# PlugEVSE_Main.net
KiCad netlist of a schematic drawn in EAGLE
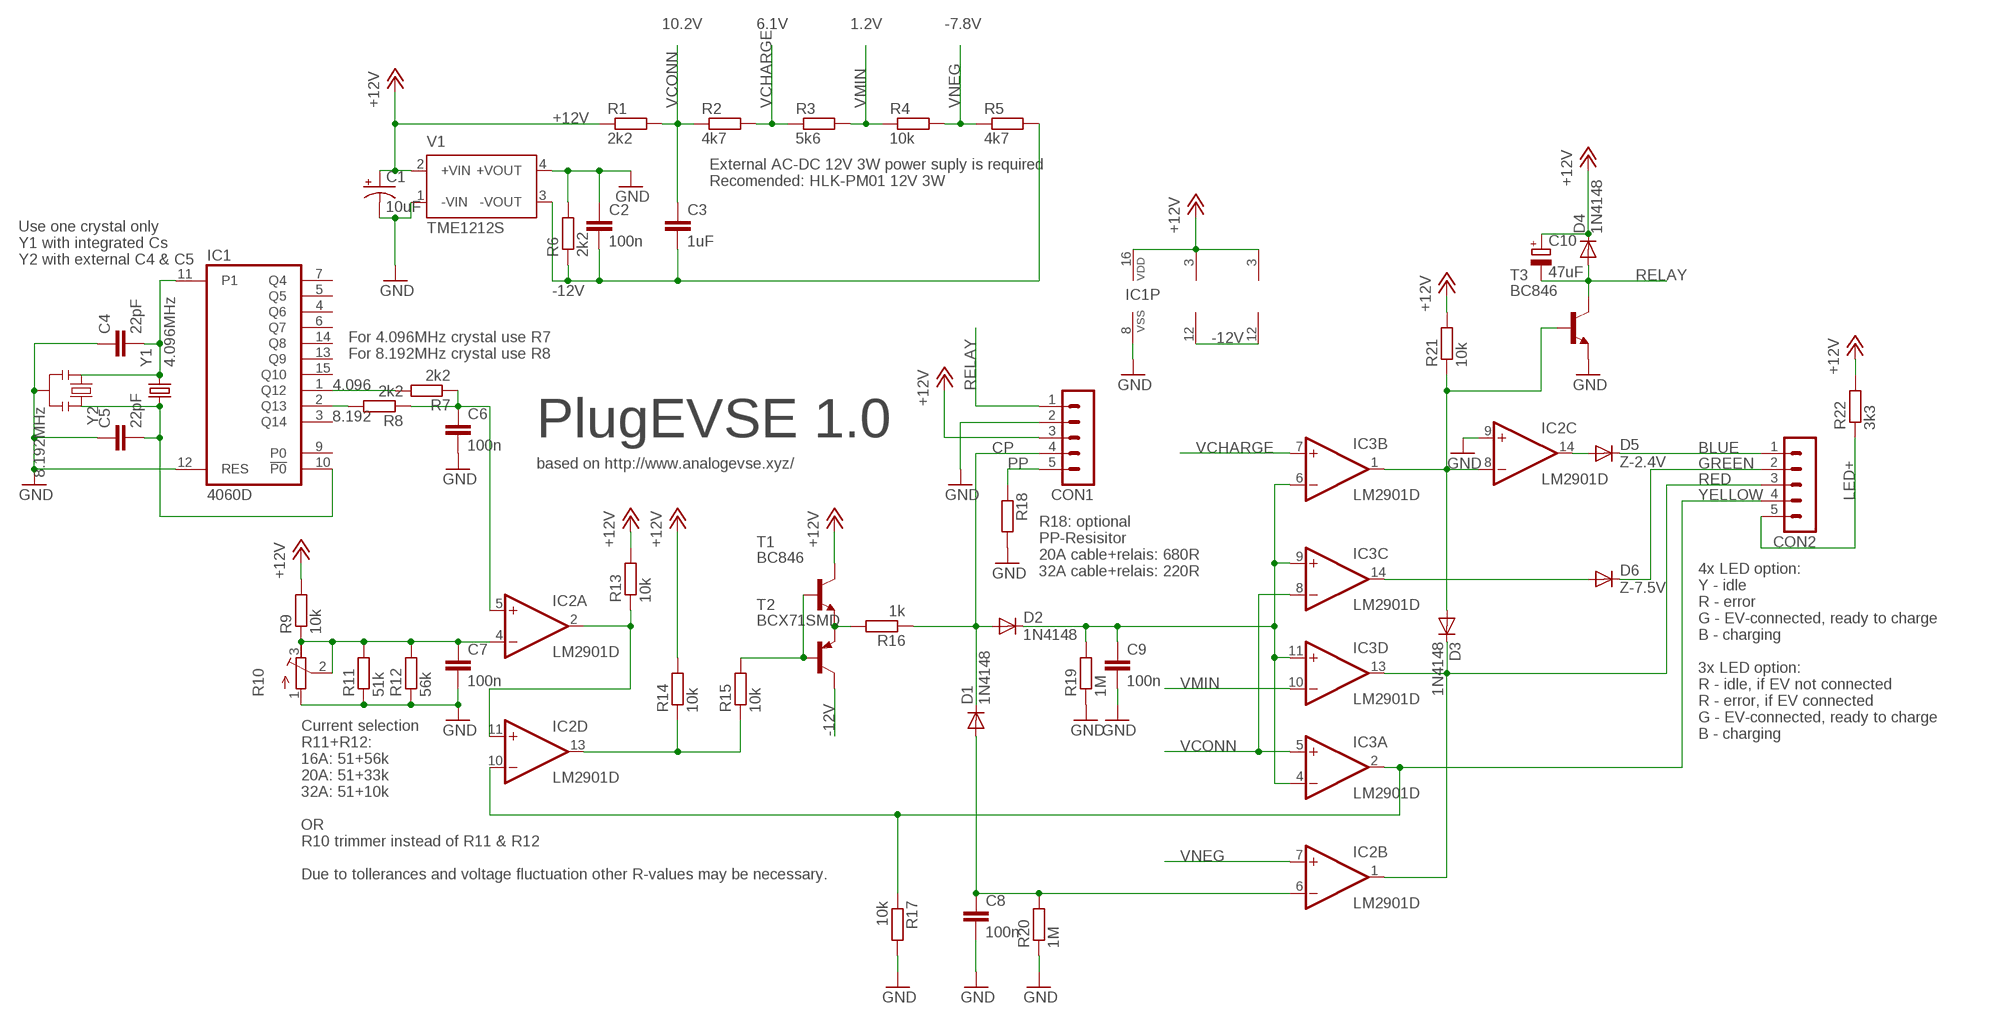
[diagram p0: schematic, sheet 1]

(export (version "E")
  (design (tool "Eeschema 10.0.6"))
  (components
    (comp (ref "C1")
      (value "10uF")
      (footprint "eagle-import:EIA3216")
      (libsource (lib "eagle-import") (part "CAP_POL1206"))
    )
    (comp (ref "C2")
      (value "100n")
      (footprint "eagle-import:C0603")
      (libsource (lib "eagle-import") (part "C-EUC0603"))
    )
    (comp (ref "C3")
      (value "1uF")
      (footprint "eagle-import:C0603")
      (libsource (lib "eagle-import") (part "C-EUC0603"))
    )
    (comp (ref "C4")
      (value "22pF")
      (footprint "eagle-import:C0603")
      (libsource (lib "eagle-import") (part "C-EUC0603"))
    )
    (comp (ref "C5")
      (value "22pF")
      (footprint "eagle-import:C0603")
      (libsource (lib "eagle-import") (part "C-EUC0603"))
    )
    (comp (ref "C6")
      (value "100n")
      (footprint "eagle-import:C0603")
      (libsource (lib "eagle-import") (part "C-EUC0603"))
    )
    (comp (ref "C7")
      (value "100n")
      (footprint "eagle-import:C0603")
      (libsource (lib "eagle-import") (part "C-EUC0603"))
    )
    (comp (ref "C8")
      (value "100n")
      (footprint "eagle-import:C0603")
      (libsource (lib "eagle-import") (part "C-EUC0603"))
    )
    (comp (ref "C9")
      (value "100n")
      (footprint "eagle-import:C0603")
      (libsource (lib "eagle-import") (part "C-EUC0603"))
    )
    (comp (ref "C10")
      (value "47uF")
      (footprint "eagle-import:E2,5-5")
      (libsource (lib "eagle-import") (part "CPOL-EUE2.5-5"))
    )
    (comp (ref "CON1")
      (value "MA05-1")
      (footprint "eagle-import:MA05-1")
      (libsource (lib "eagle-import") (part "MA05-1"))
    )
    (comp (ref "CON2")
      (value "MA05-1")
      (footprint "eagle-import:MA05-1")
      (libsource (lib "eagle-import") (part "MA05-1"))
    )
    (comp (ref "D1")
      (value "1N4148")
      (footprint "eagle-import:SOD123")
      (libsource (lib "eagle-import") (part "DIODE-SOD123"))
    )
    (comp (ref "D2")
      (value "1N4148")
      (footprint "eagle-import:SOD123")
      (libsource (lib "eagle-import") (part "DIODE-SOD123"))
    )
    (comp (ref "D3")
      (value "1N4148")
      (footprint "eagle-import:SOD123")
      (libsource (lib "eagle-import") (part "DIODE-SOD123"))
    )
    (comp (ref "D4")
      (value "1N4148")
      (footprint "eagle-import:SOD123")
      (libsource (lib "eagle-import") (part "DIODE-SOD123"))
    )
    (comp (ref "D5")
      (value "Z-2.4V")
      (footprint "eagle-import:SOD123")
      (libsource (lib "eagle-import") (part "DIODE-SOD123"))
    )
    (comp (ref "D6")
      (value "Z-7.5V")
      (footprint "eagle-import:SOD123")
      (libsource (lib "eagle-import") (part "DIODE-SOD123"))
    )
    (comp (ref "IC1")
      (value "4060D")
      (footprint "eagle-import:SO16")
      (libsource (lib "eagle-import") (part "4060D"))
    )
    (comp (ref "IC2")
      (value "LM2901D")
      (footprint "eagle-import:SO14")
      (libsource (lib "eagle-import") (part "LM2901D"))
    )
    (comp (ref "IC3")
      (value "LM2901D")
      (footprint "eagle-import:SO14")
      (libsource (lib "eagle-import") (part "LM2901D"))
    )
    (comp (ref "R1")
      (value "2k2")
      (footprint "eagle-import:R0603")
      (libsource (lib "eagle-import") (part "rcl_334_R-EU_R0603"))
    )
    (comp (ref "R2")
      (value "4k7")
      (footprint "eagle-import:R0603")
      (libsource (lib "eagle-import") (part "rcl_334_R-EU_R0603"))
    )
    (comp (ref "R3")
      (value "5k6")
      (footprint "eagle-import:R0603")
      (libsource (lib "eagle-import") (part "rcl_334_R-EU_R0603"))
    )
    (comp (ref "R4")
      (value "10k")
      (footprint "eagle-import:R0603")
      (libsource (lib "eagle-import") (part "rcl_334_R-EU_R0603"))
    )
    (comp (ref "R5")
      (value "4k7")
      (footprint "eagle-import:R0603")
      (libsource (lib "eagle-import") (part "rcl_334_R-EU_R0603"))
    )
    (comp (ref "R6")
      (value "2k2")
      (footprint "eagle-import:R0603")
      (libsource (lib "eagle-import") (part "rcl_334_R-EU_R0603"))
    )
    (comp (ref "R7")
      (value "2k2")
      (footprint "eagle-import:R0603")
      (libsource (lib "eagle-import") (part "rcl_334_R-EU_R0603"))
    )
    (comp (ref "R8")
      (value "2k2")
      (footprint "eagle-import:R0603")
      (libsource (lib "eagle-import") (part "rcl_334_R-EU_R0603"))
    )
    (comp (ref "R9")
      (value "10k")
      (footprint "eagle-import:R0603")
      (libsource (lib "eagle-import") (part "rcl_334_R-EU_R0603"))
    )
    (comp (ref "R10")
      (value "R-TRIMM3202")
      (footprint "eagle-import:RTRIM3202")
      (libsource (lib "eagle-import") (part "R-TRIMM3202"))
    )
    (comp (ref "R11")
      (value "51k")
      (footprint "eagle-import:R0603")
      (libsource (lib "eagle-import") (part "rcl_334_R-EU_R0603"))
    )
    (comp (ref "R12")
      (value "56k")
      (footprint "eagle-import:R0603")
      (libsource (lib "eagle-import") (part "rcl_334_R-EU_R0603"))
    )
    (comp (ref "R13")
      (value "10k")
      (footprint "eagle-import:R0603")
      (libsource (lib "eagle-import") (part "rcl_334_R-EU_R0603"))
    )
    (comp (ref "R14")
      (value "10k")
      (footprint "eagle-import:R0603")
      (libsource (lib "eagle-import") (part "rcl_334_R-EU_R0603"))
    )
    (comp (ref "R15")
      (value "10k")
      (footprint "eagle-import:R0603")
      (libsource (lib "eagle-import") (part "rcl_334_R-EU_R0603"))
    )
    (comp (ref "R16")
      (value "1k")
      (footprint "eagle-import:R0603")
      (libsource (lib "eagle-import") (part "rcl_334_R-EU_R0603"))
    )
    (comp (ref "R17")
      (value "10k")
      (footprint "eagle-import:R0603")
      (libsource (lib "eagle-import") (part "rcl_334_R-EU_R0603"))
    )
    (comp (ref "R18")
      (value "R-EU_R2512")
      (footprint "eagle-import:R2512")
      (libsource (lib "eagle-import") (part "R-EU_R2512"))
    )
    (comp (ref "R19")
      (value "1M")
      (footprint "eagle-import:R0603")
      (libsource (lib "eagle-import") (part "rcl_334_R-EU_R0603"))
    )
    (comp (ref "R20")
      (value "1M")
      (footprint "eagle-import:R0603")
      (libsource (lib "eagle-import") (part "rcl_334_R-EU_R0603"))
    )
    (comp (ref "R21")
      (value "10k")
      (footprint "eagle-import:R0603")
      (libsource (lib "eagle-import") (part "rcl_334_R-EU_R0603"))
    )
    (comp (ref "R22")
      (value "3k3")
      (footprint "eagle-import:R0603")
      (libsource (lib "eagle-import") (part "rcl_334_R-EU_R0603"))
    )
    (comp (ref "T1")
      (value "BC846")
      (footprint "eagle-import:SOT23")
      (libsource (lib "eagle-import") (part "BC846"))
    )
    (comp (ref "T2")
      (value "BCX71SMD")
      (footprint "eagle-import:SOT23")
      (libsource (lib "eagle-import") (part "BCX71SMD"))
    )
    (comp (ref "T3")
      (value "BC846")
      (footprint "eagle-import:SOT23")
      (libsource (lib "eagle-import") (part "BC846"))
    )
    (comp (ref "V1")
      (value "TME1212S")
      (footprint "eagle-import:TME")
      (fields (field (name "MPN") "TME 1212S"))
      (libsource (lib "eagle-import") (part "TME?1212S"))
    )
    (comp (ref "Y1")
      (value "4.096MHz")
      (footprint "eagle-import:11.4X4.5")
      (libsource (lib "eagle-import") (part "KX-K"))
    )
    (comp (ref "Y2")
      (value "8.192MHz")
      (footprint "eagle-import:RESONATOR-SMD")
      (libsource (lib "eagle-import") (part "RESONATORSMD"))
    )
  )
  (nets
    (net (code "1") (name "+12V") (class "Default")
      (node (ref "C1") (pin "A") (pinfunction "+_A") (pintype "passive"))
      (node (ref "C10") (pin "+") (pinfunction "+_+") (pintype "passive"))
      (node (ref "CON1") (pin "3") (pinfunction "3_3") (pintype "passive"))
      (node (ref "D4") (pin "C") (pinfunction "C_C") (pintype "passive"))
      (node (ref "IC1") (pin "16") (pinfunction "VDD_16") (pintype "power_in"))
      (node (ref "IC2") (pin "3") (pinfunction "V+_3") (pintype "power_in"))
      (node (ref "IC3") (pin "3") (pinfunction "V+_3") (pintype "power_in"))
      (node (ref "R1") (pin "1") (pinfunction "1_1") (pintype "passive"))
      (node (ref "R13") (pin "2") (pinfunction "2_2") (pintype "passive"))
      (node (ref "R14") (pin "2") (pinfunction "2_2") (pintype "passive"))
      (node (ref "R21") (pin "2") (pinfunction "2_2") (pintype "passive"))
      (node (ref "R22") (pin "2") (pinfunction "2_2") (pintype "passive"))
      (node (ref "R9") (pin "2") (pinfunction "2_2") (pintype "passive"))
      (node (ref "T1") (pin "3") (pinfunction "C_3") (pintype "passive"))
      (node (ref "V1") (pin "2") (pinfunction "+VIN_2") (pintype "passive"))
    )
    (net (code "2") (name "/-12V") (class "Default")
      (node (ref "C2") (pin "2") (pinfunction "2_2") (pintype "passive"))
      (node (ref "C3") (pin "2") (pinfunction "2_2") (pintype "passive"))
      (node (ref "IC2") (pin "12") (pinfunction "V-_12") (pintype "power_in"))
      (node (ref "IC3") (pin "12") (pinfunction "V-_12") (pintype "power_in"))
      (node (ref "R5") (pin "2") (pinfunction "2_2") (pintype "passive"))
      (node (ref "R6") (pin "1") (pinfunction "1_1") (pintype "passive"))
      (node (ref "T2") (pin "3") (pinfunction "C_3") (pintype "passive"))
      (node (ref "V1") (pin "3") (pinfunction "-VOUT_3") (pintype "passive"))
    )
    (net (code "3") (name "/BLUE") (class "Default")
      (node (ref "CON2") (pin "1") (pinfunction "1_1") (pintype "passive"))
      (node (ref "D5") (pin "C") (pinfunction "C_C") (pintype "passive"))
    )
    (net (code "4") (name "/CP") (class "Default")
      (node (ref "CON1") (pin "4") (pinfunction "4_4") (pintype "passive"))
      (node (ref "D1") (pin "C") (pinfunction "C_C") (pintype "passive"))
      (node (ref "D2") (pin "A") (pinfunction "A_A") (pintype "passive"))
      (node (ref "R16") (pin "1") (pinfunction "1_1") (pintype "passive"))
    )
    (net (code "5") (name "/GREEN") (class "Default")
      (node (ref "CON2") (pin "2") (pinfunction "2_2") (pintype "passive"))
      (node (ref "D6") (pin "C") (pinfunction "C_C") (pintype "passive"))
    )
    (net (code "6") (name "/LED+") (class "Default")
      (node (ref "CON2") (pin "5") (pinfunction "5_5") (pintype "passive"))
      (node (ref "R22") (pin "1") (pinfunction "1_1") (pintype "passive"))
    )
    (net (code "7") (name "/PP") (class "Default")
      (node (ref "CON1") (pin "5") (pinfunction "5_5") (pintype "passive"))
      (node (ref "R18") (pin "1") (pinfunction "1_1") (pintype "passive"))
    )
    (net (code "8") (name "/RED") (class "Default")
      (node (ref "CON2") (pin "3") (pinfunction "3_3") (pintype "passive"))
      (node (ref "D3") (pin "C") (pinfunction "C_C") (pintype "passive"))
      (node (ref "IC2") (pin "1") (pinfunction "OUT_1") (pintype "output"))
      (node (ref "IC3") (pin "13") (pinfunction "OUT_13") (pintype "output"))
    )
    (net (code "9") (name "/RELAY") (class "Default")
      (node (ref "C10") (pin "-") (pinfunction "-_-") (pintype "passive"))
      (node (ref "CON1") (pin "1") (pinfunction "1_1") (pintype "passive"))
      (node (ref "D4") (pin "A") (pinfunction "A_A") (pintype "passive"))
      (node (ref "T3") (pin "3") (pinfunction "C_3") (pintype "passive"))
    )
    (net (code "10") (name "/VCHARGE") (class "Default")
      (node (ref "IC3") (pin "7") (pinfunction "+IN_7") (pintype "input"))
      (node (ref "R2") (pin "2") (pinfunction "2_2") (pintype "passive"))
      (node (ref "R3") (pin "1") (pinfunction "1_1") (pintype "passive"))
    )
    (net (code "11") (name "/VCONN") (class "Default")
      (node (ref "C3") (pin "1") (pinfunction "1_1") (pintype "passive"))
      (node (ref "IC3") (pin "5") (pinfunction "+IN_5") (pintype "input"))
      (node (ref "IC3") (pin "8") (pinfunction "-IN_8") (pintype "input"))
      (node (ref "R1") (pin "2") (pinfunction "2_2") (pintype "passive"))
      (node (ref "R2") (pin "1") (pinfunction "1_1") (pintype "passive"))
    )
    (net (code "12") (name "/VMIN") (class "Default")
      (node (ref "IC3") (pin "10") (pinfunction "-IN_10") (pintype "input"))
      (node (ref "R3") (pin "2") (pinfunction "2_2") (pintype "passive"))
      (node (ref "R4") (pin "1") (pinfunction "1_1") (pintype "passive"))
    )
    (net (code "13") (name "/VNEG") (class "Default")
      (node (ref "IC2") (pin "7") (pinfunction "+IN_7") (pintype "input"))
      (node (ref "R4") (pin "2") (pinfunction "2_2") (pintype "passive"))
      (node (ref "R5") (pin "1") (pinfunction "1_1") (pintype "passive"))
    )
    (net (code "14") (name "/YELLOW") (class "Default")
      (node (ref "CON2") (pin "4") (pinfunction "4_4") (pintype "passive"))
      (node (ref "IC2") (pin "10") (pinfunction "-IN_10") (pintype "input"))
      (node (ref "IC3") (pin "2") (pinfunction "OUT_2") (pintype "output"))
      (node (ref "R17") (pin "1") (pinfunction "1_1") (pintype "passive"))
    )
    (net (code "15") (name "GND") (class "Default")
      (node (ref "C1") (pin "C") (pinfunction "-_C") (pintype "passive"))
      (node (ref "C2") (pin "1") (pinfunction "1_1") (pintype "passive"))
      (node (ref "C4") (pin "1") (pinfunction "1_1") (pintype "passive"))
      (node (ref "C5") (pin "1") (pinfunction "1_1") (pintype "passive"))
      (node (ref "C6") (pin "2") (pinfunction "2_2") (pintype "passive"))
      (node (ref "C7") (pin "2") (pinfunction "2_2") (pintype "passive"))
      (node (ref "C8") (pin "2") (pinfunction "2_2") (pintype "passive"))
      (node (ref "C9") (pin "2") (pinfunction "2_2") (pintype "passive"))
      (node (ref "CON1") (pin "2") (pinfunction "2_2") (pintype "passive"))
      (node (ref "IC1") (pin "12") (pinfunction "RES_12") (pintype "input"))
      (node (ref "IC1") (pin "8") (pinfunction "VSS_8") (pintype "power_in"))
      (node (ref "IC2") (pin "9") (pinfunction "+IN_9") (pintype "input"))
      (node (ref "R10") (pin "1") (pinfunction "A_1") (pintype "passive"))
      (node (ref "R11") (pin "1") (pinfunction "1_1") (pintype "passive"))
      (node (ref "R12") (pin "1") (pinfunction "1_1") (pintype "passive"))
      (node (ref "R17") (pin "2") (pinfunction "2_2") (pintype "passive"))
      (node (ref "R18") (pin "2") (pinfunction "2_2") (pintype "passive"))
      (node (ref "R19") (pin "1") (pinfunction "1_1") (pintype "passive"))
      (node (ref "R20") (pin "1") (pinfunction "1_1") (pintype "passive"))
      (node (ref "R6") (pin "2") (pinfunction "2_2") (pintype "passive"))
      (node (ref "T3") (pin "2") (pinfunction "E_2") (pintype "passive"))
      (node (ref "V1") (pin "1") (pinfunction "-VIN_1") (pintype "passive"))
      (node (ref "V1") (pin "4") (pinfunction "+VOUT_4") (pintype "passive"))
      (node (ref "Y2") (pin "2") (pinfunction "2_2") (pintype "passive"))
    )
    (net (code "16") (name "Net-(IC1A-P1)") (class "Default")
      (node (ref "C4") (pin "2") (pinfunction "2_2") (pintype "passive"))
      (node (ref "IC1") (pin "11") (pinfunction "P1_11") (pintype "input"))
      (node (ref "Y1") (pin "2") (pinfunction "2_2") (pintype "passive"))
      (node (ref "Y2") (pin "1") (pinfunction "1_1") (pintype "passive"))
    )
    (net (code "17") (name "Net-(IC1A-Q12)") (class "Default")
      (node (ref "IC1") (pin "1") (pinfunction "Q12_1") (pintype "output"))
      (node (ref "R7") (pin "2") (pinfunction "2_2") (pintype "passive"))
    )
    (net (code "18") (name "Net-(IC1A-Q13)") (class "Default")
      (node (ref "IC1") (pin "2") (pinfunction "Q13_2") (pintype "output"))
      (node (ref "R8") (pin "2") (pinfunction "2_2") (pintype "passive"))
    )
    (net (code "19") (name "Net-(IC1A-~{P0})") (class "Default")
      (node (ref "C5") (pin "2") (pinfunction "2_2") (pintype "passive"))
      (node (ref "IC1") (pin "10") (pinfunction "~{P0}_10") (pintype "output"))
      (node (ref "Y1") (pin "1") (pinfunction "1_1") (pintype "passive"))
      (node (ref "Y2") (pin "3") (pinfunction "3_3") (pintype "passive"))
    )
    (net (code "20") (name "Net-(IC2A-+IN)") (class "Default")
      (node (ref "C6") (pin "1") (pinfunction "1_1") (pintype "passive"))
      (node (ref "IC2") (pin "5") (pinfunction "+IN_5") (pintype "input"))
      (node (ref "R7") (pin "1") (pinfunction "1_1") (pintype "passive"))
      (node (ref "R8") (pin "1") (pinfunction "1_1") (pintype "passive"))
    )
    (net (code "21") (name "Net-(IC2A--IN)") (class "Default")
      (node (ref "C7") (pin "1") (pinfunction "1_1") (pintype "passive"))
      (node (ref "IC2") (pin "4") (pinfunction "-IN_4") (pintype "input"))
      (node (ref "R10") (pin "2") (pinfunction "S_2") (pintype "passive"))
      (node (ref "R10") (pin "3") (pinfunction "E_3") (pintype "passive"))
      (node (ref "R11") (pin "2") (pinfunction "2_2") (pintype "passive"))
      (node (ref "R12") (pin "2") (pinfunction "2_2") (pintype "passive"))
      (node (ref "R9") (pin "1") (pinfunction "1_1") (pintype "passive"))
    )
    (net (code "22") (name "Net-(IC2A-OUT)") (class "Default")
      (node (ref "IC2") (pin "11") (pinfunction "+IN_11") (pintype "input"))
      (node (ref "IC2") (pin "2") (pinfunction "OUT_2") (pintype "output"))
      (node (ref "R13") (pin "1") (pinfunction "1_1") (pintype "passive"))
    )
    (net (code "23") (name "Net-(IC2B--IN)") (class "Default")
      (node (ref "C8") (pin "1") (pinfunction "1_1") (pintype "passive"))
      (node (ref "D1") (pin "A") (pinfunction "A_A") (pintype "passive"))
      (node (ref "IC2") (pin "6") (pinfunction "-IN_6") (pintype "input"))
      (node (ref "R20") (pin "2") (pinfunction "2_2") (pintype "passive"))
    )
    (net (code "24") (name "Net-(IC2C--IN)") (class "Default")
      (node (ref "D3") (pin "A") (pinfunction "A_A") (pintype "passive"))
      (node (ref "IC2") (pin "8") (pinfunction "-IN_8") (pintype "input"))
      (node (ref "IC3") (pin "1") (pinfunction "OUT_1") (pintype "output"))
      (node (ref "R21") (pin "1") (pinfunction "1_1") (pintype "passive"))
      (node (ref "T3") (pin "1") (pinfunction "B_1") (pintype "passive"))
    )
    (net (code "25") (name "Net-(IC2C-OUT)") (class "Default")
      (node (ref "D5") (pin "A") (pinfunction "A_A") (pintype "passive"))
      (node (ref "IC2") (pin "14") (pinfunction "OUT_14") (pintype "output"))
    )
    (net (code "26") (name "Net-(IC2D-OUT)") (class "Default")
      (node (ref "IC2") (pin "13") (pinfunction "OUT_13") (pintype "output"))
      (node (ref "R14") (pin "1") (pinfunction "1_1") (pintype "passive"))
      (node (ref "R15") (pin "1") (pinfunction "1_1") (pintype "passive"))
    )
    (net (code "27") (name "Net-(IC3A--IN)") (class "Default")
      (node (ref "C9") (pin "1") (pinfunction "1_1") (pintype "passive"))
      (node (ref "D2") (pin "C") (pinfunction "C_C") (pintype "passive"))
      (node (ref "IC3") (pin "11") (pinfunction "+IN_11") (pintype "input"))
      (node (ref "IC3") (pin "4") (pinfunction "-IN_4") (pintype "input"))
      (node (ref "IC3") (pin "6") (pinfunction "-IN_6") (pintype "input"))
      (node (ref "IC3") (pin "9") (pinfunction "+IN_9") (pintype "input"))
      (node (ref "R19") (pin "2") (pinfunction "2_2") (pintype "passive"))
    )
    (net (code "28") (name "Net-(IC3C-OUT)") (class "Default")
      (node (ref "D6") (pin "A") (pinfunction "A_A") (pintype "passive"))
      (node (ref "IC3") (pin "14") (pinfunction "OUT_14") (pintype "output"))
    )
    (net (code "29") (name "Net-(T1-B)") (class "Default")
      (node (ref "R15") (pin "2") (pinfunction "2_2") (pintype "passive"))
      (node (ref "T1") (pin "1") (pinfunction "B_1") (pintype "passive"))
      (node (ref "T2") (pin "1") (pinfunction "B_1") (pintype "passive"))
    )
    (net (code "30") (name "Net-(T1-E)") (class "Default")
      (node (ref "R16") (pin "2") (pinfunction "2_2") (pintype "passive"))
      (node (ref "T1") (pin "2") (pinfunction "E_2") (pintype "passive"))
      (node (ref "T2") (pin "2") (pinfunction "E_2") (pintype "passive"))
    )
    (net (code "31") (name "unconnected-(IC1A-P0-Pad9)") (class "Default")
      (node (ref "IC1") (pin "9") (pinfunction "P0_9") (pintype "output"))
    )
    (net (code "32") (name "unconnected-(IC1A-Q4-Pad7)") (class "Default")
      (node (ref "IC1") (pin "7") (pinfunction "Q4_7") (pintype "output"))
    )
    (net (code "33") (name "unconnected-(IC1A-Q5-Pad5)") (class "Default")
      (node (ref "IC1") (pin "5") (pinfunction "Q5_5") (pintype "output"))
    )
    (net (code "34") (name "unconnected-(IC1A-Q6-Pad4)") (class "Default")
      (node (ref "IC1") (pin "4") (pinfunction "Q6_4") (pintype "output"))
    )
    (net (code "35") (name "unconnected-(IC1A-Q7-Pad6)") (class "Default")
      (node (ref "IC1") (pin "6") (pinfunction "Q7_6") (pintype "output"))
    )
    (net (code "36") (name "unconnected-(IC1A-Q8-Pad14)") (class "Default")
      (node (ref "IC1") (pin "14") (pinfunction "Q8_14") (pintype "output"))
    )
    (net (code "37") (name "unconnected-(IC1A-Q9-Pad13)") (class "Default")
      (node (ref "IC1") (pin "13") (pinfunction "Q9_13") (pintype "output"))
    )
    (net (code "38") (name "unconnected-(IC1A-Q10-Pad15)") (class "Default")
      (node (ref "IC1") (pin "15") (pinfunction "Q10_15") (pintype "output"))
    )
    (net (code "39") (name "unconnected-(IC1A-Q14-Pad3)") (class "Default")
      (node (ref "IC1") (pin "3") (pinfunction "Q14_3") (pintype "output"))
    )
  )
)
